# 07_USB.net
KiCad netlist of a schematic drawn in Altium Designer
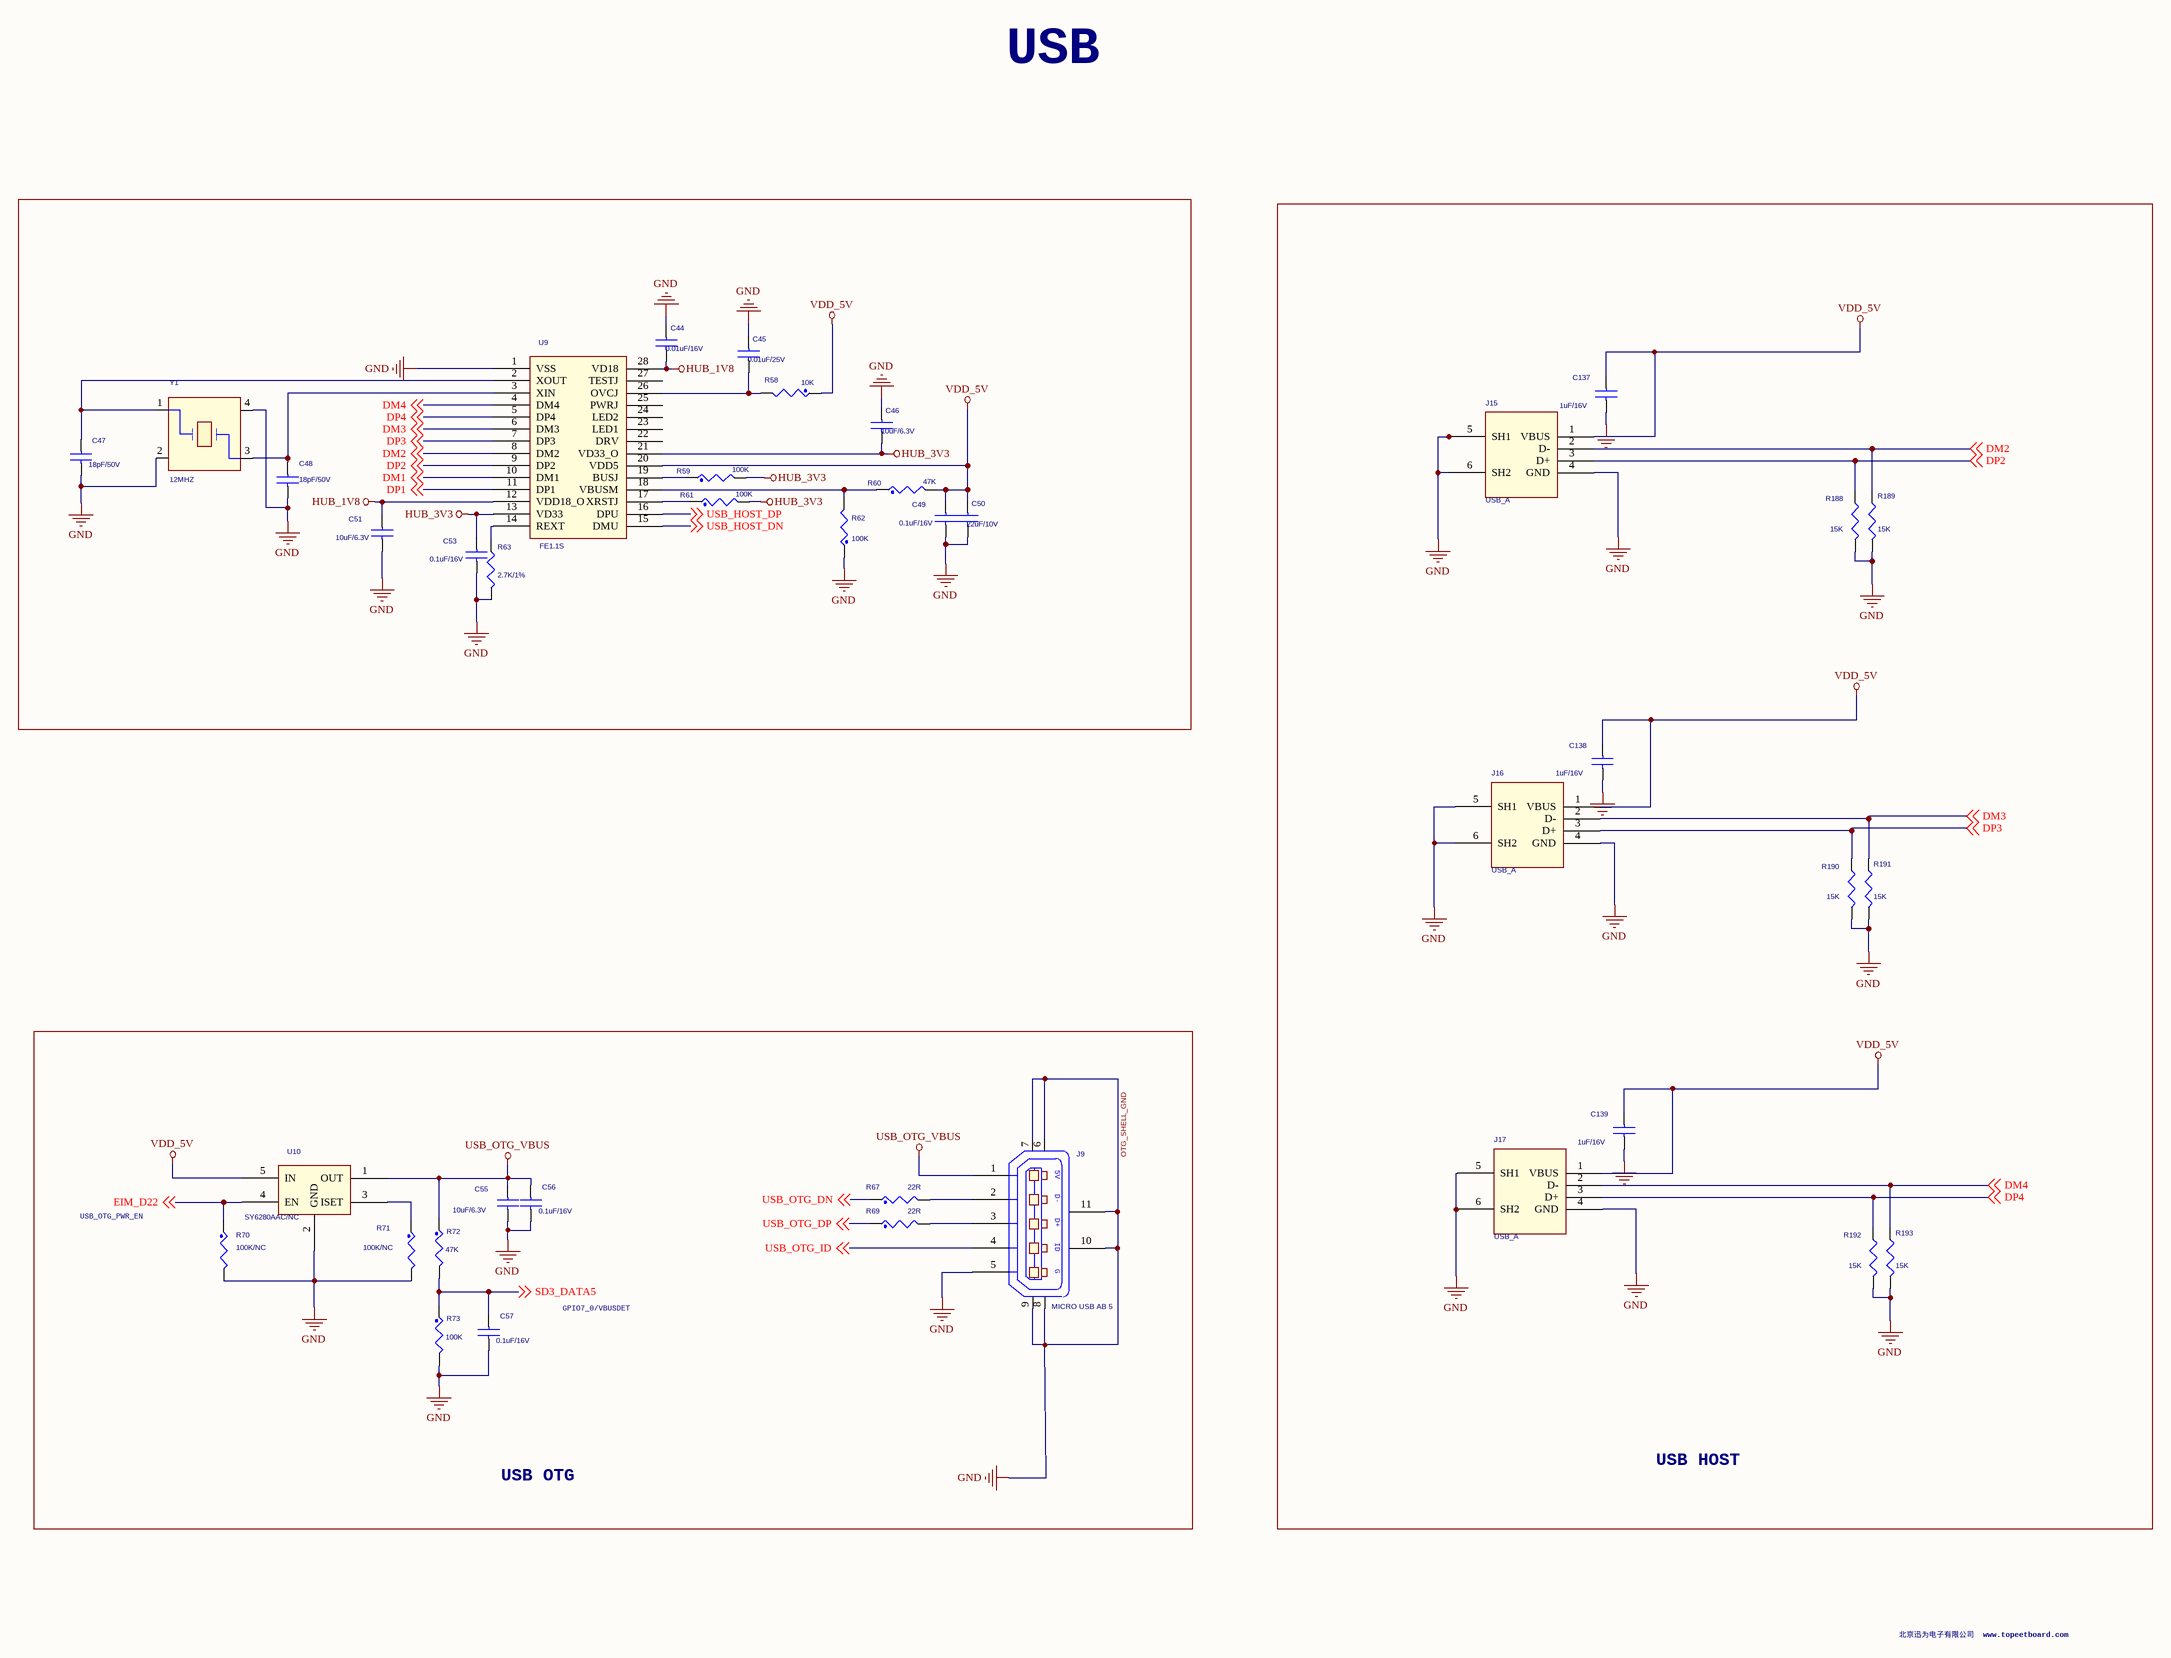
[diagram p0: 07 USB.SchDoc]

(export (version "E")
  (design (tool "Eeschema 10.0.6"))
  (components
    (comp (ref "C44") (value "0.01uF/16V") (footprint "C0603") (libsource (lib "*") (part "C0603_0_Dup1")))
    (comp (ref "C45") (value "0.01uF/25V") (footprint "C0603") (libsource (lib "*") (part "C0603_0_Dup1")))
    (comp (ref "C46") (value "10uF/6.3V") (footprint "C0603") (libsource (lib "*") (part "C0603_0_Dup1")))
    (comp (ref "C47") (value "18pF/50V") (footprint "C0603") (libsource (lib "*") (part "C0603_0_Dup1")))
    (comp (ref "C48") (value "18pF/50V") (footprint "C0603") (libsource (lib "*") (part "C0603_0_Dup1")))
    (comp (ref "C49") (value "0.1uF/16V") (footprint "C0603") (libsource (lib "*") (part "C0603_0_Dup1")))
    (comp (ref "C50") (value "22uF/10V") (footprint "C0603") (libsource (lib "*") (part "C0603_0_Dup1")))
    (comp (ref "C51") (value "10uF/6.3V") (footprint "C0603") (libsource (lib "*") (part "C0603_0_Dup1")))
    (comp (ref "C53") (value "0.1uF/16V") (footprint "C0603") (libsource (lib "*") (part "C0603_0_Dup1")))
    (comp (ref "C55") (value "10uF/6.3V") (footprint "C0603") (libsource (lib "*") (part "C0603_0_Dup1")))
    (comp (ref "C56") (value "0.1uF/16V") (footprint "C0603") (libsource (lib "*") (part "C0603_0_Dup1")))
    (comp (ref "C57") (value "0.1uF/16V") (footprint "C0603") (libsource (lib "*") (part "C0603_0_Dup1")))
    (comp (ref "C137") (value "1uF/16V") (footprint "C0603") (libsource (lib "*") (part "C0603_0_Dup1")))
    (comp (ref "C138") (value "1uF/16V") (footprint "C0603") (libsource (lib "*") (part "C0603_0_Dup1")))
    (comp (ref "C139") (value "1uF/16V") (footprint "C0603") (libsource (lib "*") (part "C0603_0_Dup1")))
    (comp (ref "J9")
      (value "MICRO USB AB 5")
      (description "CON 1X5 USB_MICRO_AB_RECEPTACLE RA SMT 0.65MM SP 105H AU")
      (libsource (lib "*") (part "USB_MINI_AB_RECEPTACLE_1"))
    )
    (comp (ref "J15") (value "USB_A") (libsource (lib "*") (part "USB")))
    (comp (ref "J16") (value "USB_A") (libsource (lib "*") (part "USB")))
    (comp (ref "J17") (value "USB_A") (libsource (lib "*") (part "USB")))
    (comp (ref "R58")
      (value "10K")
      (description "RES MF 10.0K 1/16W 1% AEC-Q200 0402")
      (fields (field (name "TOLERANCE") "1%"))
      (libsource (lib "*") (part "RES_Dup1"))
    )
    (comp (ref "R59")
      (value "100K")
      (description "RES MF 10.0K 1/16W 1% AEC-Q200 0402")
      (fields (field (name "TOLERANCE") "1%"))
      (libsource (lib "*") (part "RES_Dup1"))
    )
    (comp (ref "R60")
      (value "47K")
      (description "RES MF 10.0K 1/16W 1% AEC-Q200 0402")
      (fields (field (name "TOLERANCE") "1%"))
      (libsource (lib "*") (part "RES_Dup1"))
    )
    (comp (ref "R61")
      (value "100K")
      (description "RES MF 10.0K 1/16W 1% AEC-Q200 0402")
      (fields (field (name "TOLERANCE") "1%"))
      (libsource (lib "*") (part "RES_Dup1"))
    )
    (comp (ref "R62")
      (value "100K")
      (description "RES MF 10.0K 1/16W 1% AEC-Q200 0402")
      (fields (field (name "TOLERANCE") "1%"))
      (libsource (lib "*") (part "RES_Dup1"))
    )
    (comp (ref "R63") (value "2.7K/1%") (footprint "R1005") (libsource (lib "*") (part "R1005_0_Dup1")))
    (comp (ref "R67")
      (value "22R")
      (description "RES MF 10.0K 1/16W 1% AEC-Q200 0402")
      (fields (field (name "TOLERANCE") "1%"))
      (libsource (lib "*") (part "RES_Dup1"))
    )
    (comp (ref "R69")
      (value "22R")
      (description "RES MF 10.0K 1/16W 1% AEC-Q200 0402")
      (fields (field (name "TOLERANCE") "1%"))
      (libsource (lib "*") (part "RES_Dup1"))
    )
    (comp (ref "R70")
      (value "100K/NC")
      (description "RES MF 10.0K 1/16W 1% AEC-Q200 0402")
      (fields (field (name "TOLERANCE") "1%"))
      (libsource (lib "*") (part "RES_Dup1"))
    )
    (comp (ref "R71")
      (value "100K/NC")
      (description "RES MF 10.0K 1/16W 1% AEC-Q200 0402")
      (fields (field (name "TOLERANCE") "1%"))
      (libsource (lib "*") (part "RES_Dup1"))
    )
    (comp (ref "R72")
      (value "47K")
      (description "RES MF 10.0K 1/16W 1% AEC-Q200 0402")
      (fields (field (name "TOLERANCE") "1%"))
      (libsource (lib "*") (part "RES_Dup1"))
    )
    (comp (ref "R73")
      (value "100K")
      (description "RES MF 10.0K 1/16W 1% AEC-Q200 0402")
      (fields (field (name "TOLERANCE") "1%"))
      (libsource (lib "*") (part "RES_Dup1"))
    )
    (comp (ref "R188") (value "15K") (footprint "R1005") (libsource (lib "*") (part "R1005_0_Dup1")))
    (comp (ref "R189") (value "15K") (footprint "R1005") (libsource (lib "*") (part "R1005_0_Dup1")))
    (comp (ref "R190") (value "15K") (footprint "R1005") (libsource (lib "*") (part "R1005_0_Dup1")))
    (comp (ref "R191") (value "15K") (footprint "R1005") (libsource (lib "*") (part "R1005_0_Dup1")))
    (comp (ref "R192") (value "15K") (footprint "R1005") (libsource (lib "*") (part "R1005_0_Dup1")))
    (comp (ref "R193") (value "15K") (footprint "R1005") (libsource (lib "*") (part "R1005_0_Dup1")))
    (comp (ref "U9") (value "FE1.1S") (libsource (lib "*") (part "FE1.1S")))
    (comp (ref "U10") (value "SY6280AAC/NC") (libsource (lib "*") (part "SY6280AAC")))
    (comp (ref "Y1")
      (value "12MHZ")
      (description "XTAL 25MHZ -- -- SMT")
      (libsource (lib "*") (part "XTAL_13Y"))
    )
  )
  (nets
    (net (code "1") (name "DM1") (class "Default")
      (node (ref "U9") (pin "10") (pinfunction "DM1_10") (pintype "passive"))
    )
    (net (code "2") (name "DM2") (class "Default")
      (node (ref "J15") (pin "2") (pinfunction "D-_2") (pintype "passive"))
      (node (ref "R189") (pin "2") (pinfunction "2_2") (pintype "passive"))
      (node (ref "U9") (pin "8") (pinfunction "DM2_8") (pintype "passive"))
    )
    (net (code "3") (name "DM3") (class "Default")
      (node (ref "J16") (pin "2") (pinfunction "D-_2") (pintype "passive"))
      (node (ref "R191") (pin "2") (pinfunction "2_2") (pintype "passive"))
      (node (ref "U9") (pin "6") (pinfunction "DM3_6") (pintype "passive"))
    )
    (net (code "4") (name "DM4") (class "Default")
      (node (ref "J17") (pin "2") (pinfunction "D-_2") (pintype "passive"))
      (node (ref "R193") (pin "2") (pinfunction "2_2") (pintype "passive"))
      (node (ref "U9") (pin "4") (pinfunction "DM4_4") (pintype "passive"))
    )
    (net (code "5") (name "DP1") (class "Default")
      (node (ref "U9") (pin "11") (pinfunction "DP1_11") (pintype "passive"))
    )
    (net (code "6") (name "DP2") (class "Default")
      (node (ref "J15") (pin "3") (pinfunction "D+_3") (pintype "passive"))
      (node (ref "R188") (pin "2") (pinfunction "2_2") (pintype "passive"))
      (node (ref "U9") (pin "9") (pinfunction "DP2_9") (pintype "passive"))
    )
    (net (code "7") (name "DP3") (class "Default")
      (node (ref "J16") (pin "3") (pinfunction "D+_3") (pintype "passive"))
      (node (ref "R190") (pin "2") (pinfunction "2_2") (pintype "passive"))
      (node (ref "U9") (pin "7") (pinfunction "DP3_7") (pintype "passive"))
    )
    (net (code "8") (name "DP4") (class "Default")
      (node (ref "J17") (pin "3") (pinfunction "D+_3") (pintype "passive"))
      (node (ref "R192") (pin "2") (pinfunction "2_2") (pintype "passive"))
      (node (ref "U9") (pin "5") (pinfunction "DP4_5") (pintype "passive"))
    )
    (net (code "9") (name "EIM_D22") (class "Default")
      (node (ref "R70") (pin "1") (pinfunction "1_1") (pintype "passive"))
      (node (ref "U10") (pin "4") (pinfunction "EN_4") (pintype "passive"))
    )
    (net (code "10") (name "GND") (class "Default")
      (node (ref "C137") (pin "2") (pinfunction "2_2") (pintype "passive"))
      (node (ref "C138") (pin "2") (pinfunction "2_2") (pintype "passive"))
      (node (ref "C139") (pin "2") (pinfunction "2_2") (pintype "passive"))
      (node (ref "C44") (pin "1") (pinfunction "1_1") (pintype "passive"))
      (node (ref "C45") (pin "1") (pinfunction "1_1") (pintype "passive"))
      (node (ref "C46") (pin "1") (pinfunction "1_1") (pintype "passive"))
      (node (ref "C47") (pin "2") (pinfunction "2_2") (pintype "passive"))
      (node (ref "C48") (pin "2") (pinfunction "2_2") (pintype "passive"))
      (node (ref "C49") (pin "2") (pinfunction "2_2") (pintype "passive"))
      (node (ref "C50") (pin "2") (pinfunction "2_2") (pintype "passive"))
      (node (ref "C51") (pin "2") (pinfunction "2_2") (pintype "passive"))
      (node (ref "C53") (pin "2") (pinfunction "2_2") (pintype "passive"))
      (node (ref "C55") (pin "2") (pinfunction "2_2") (pintype "passive"))
      (node (ref "C56") (pin "2") (pinfunction "2_2") (pintype "passive"))
      (node (ref "C57") (pin "2") (pinfunction "2_2") (pintype "passive"))
      (node (ref "J15") (pin "4") (pinfunction "GND_4") (pintype "passive"))
      (node (ref "J15") (pin "5") (pinfunction "SH1_5") (pintype "passive"))
      (node (ref "J15") (pin "6") (pinfunction "SH2_6") (pintype "passive"))
      (node (ref "J16") (pin "4") (pinfunction "GND_4") (pintype "passive"))
      (node (ref "J16") (pin "5") (pinfunction "SH1_5") (pintype "passive"))
      (node (ref "J16") (pin "6") (pinfunction "SH2_6") (pintype "passive"))
      (node (ref "J17") (pin "4") (pinfunction "GND_4") (pintype "passive"))
      (node (ref "J17") (pin "5") (pinfunction "SH1_5") (pintype "passive"))
      (node (ref "J17") (pin "6") (pinfunction "SH2_6") (pintype "passive"))
      (node (ref "J9") (pin "10") (pinfunction "SHLD5_10") (pintype "passive"))
      (node (ref "J9") (pin "11") (pinfunction "SHLD6_11") (pintype "passive"))
      (node (ref "J9") (pin "5") (pinfunction "P5_5") (pintype "passive"))
      (node (ref "J9") (pin "6") (pinfunction "SHLD1_6") (pintype "passive"))
      (node (ref "J9") (pin "7") (pinfunction "SHLD3_7") (pintype "passive"))
      (node (ref "J9") (pin "8") (pinfunction "SHLD2_8") (pintype "passive"))
      (node (ref "J9") (pin "9") (pinfunction "SHLD4_9") (pintype "passive"))
      (node (ref "R188") (pin "1") (pinfunction "1_1") (pintype "passive"))
      (node (ref "R189") (pin "1") (pinfunction "1_1") (pintype "passive"))
      (node (ref "R190") (pin "1") (pinfunction "1_1") (pintype "passive"))
      (node (ref "R191") (pin "1") (pinfunction "1_1") (pintype "passive"))
      (node (ref "R192") (pin "1") (pinfunction "1_1") (pintype "passive"))
      (node (ref "R193") (pin "1") (pinfunction "1_1") (pintype "passive"))
      (node (ref "R62") (pin "1") (pinfunction "1_1") (pintype "passive"))
      (node (ref "R63") (pin "1") (pinfunction "1_1") (pintype "passive"))
      (node (ref "R70") (pin "2") (pinfunction "2_2") (pintype "passive"))
      (node (ref "R71") (pin "2") (pinfunction "2_2") (pintype "passive"))
      (node (ref "R73") (pin "2") (pinfunction "2_2") (pintype "passive"))
      (node (ref "U10") (pin "2") (pinfunction "GND_2") (pintype "passive"))
      (node (ref "U9") (pin "1") (pinfunction "VSS_1") (pintype "passive"))
      (node (ref "Y1") (pin "2") (pinfunction "2_2") (pintype "passive"))
      (node (ref "Y1") (pin "4") (pinfunction "4_4") (pintype "passive"))
    )
    (net (code "11") (name "HUB_1V8") (class "Default")
      (node (ref "C44") (pin "2") (pinfunction "2_2") (pintype "passive"))
      (node (ref "C51") (pin "1") (pinfunction "1_1") (pintype "passive"))
      (node (ref "U9") (pin "12") (pinfunction "VDD18_O_12") (pintype "passive"))
      (node (ref "U9") (pin "28") (pinfunction "VD18_28") (pintype "passive"))
    )
    (net (code "12") (name "HUB_3V3") (class "Default")
      (node (ref "C46") (pin "2") (pinfunction "2_2") (pintype "passive"))
      (node (ref "C53") (pin "1") (pinfunction "1_1") (pintype "passive"))
      (node (ref "R59") (pin "2") (pinfunction "2_2") (pintype "passive"))
      (node (ref "R61") (pin "2") (pinfunction "2_2") (pintype "passive"))
      (node (ref "U9") (pin "13") (pinfunction "VD33_13") (pintype "passive"))
      (node (ref "U9") (pin "21") (pinfunction "VD33_O_21") (pintype "passive"))
    )
    (net (code "13") (name "Net-(J9-P2)") (class "Default")
      (node (ref "J9") (pin "2") (pinfunction "P2_2") (pintype "passive"))
      (node (ref "R67") (pin "2") (pinfunction "2_2") (pintype "passive"))
    )
    (net (code "14") (name "Net-(J9-P3)") (class "Default")
      (node (ref "J9") (pin "3") (pinfunction "P3_3") (pintype "passive"))
      (node (ref "R69") (pin "2") (pinfunction "2_2") (pintype "passive"))
    )
    (net (code "15") (name "Net-(U9-BUSJ)") (class "Default")
      (node (ref "R59") (pin "1") (pinfunction "1_1") (pintype "passive"))
      (node (ref "U9") (pin "19") (pinfunction "BUSJ_19") (pintype "passive"))
    )
    (net (code "16") (name "Net-(U9-OVCJ)") (class "Default")
      (node (ref "C45") (pin "2") (pinfunction "2_2") (pintype "passive"))
      (node (ref "R58") (pin "2") (pinfunction "2_2") (pintype "passive"))
      (node (ref "U9") (pin "26") (pinfunction "OVCJ_26") (pintype "passive"))
    )
    (net (code "17") (name "Net-(U9-REXT)") (class "Default")
      (node (ref "R63") (pin "2") (pinfunction "2_2") (pintype "passive"))
      (node (ref "U9") (pin "14") (pinfunction "REXT_14") (pintype "passive"))
    )
    (net (code "18") (name "Net-(U9-VBUSM)") (class "Default")
      (node (ref "R60") (pin "1") (pinfunction "1_1") (pintype "passive"))
      (node (ref "R62") (pin "2") (pinfunction "2_2") (pintype "passive"))
      (node (ref "U9") (pin "18") (pinfunction "VBUSM_18") (pintype "passive"))
    )
    (net (code "19") (name "Net-(U9-XIN)") (class "Default")
      (node (ref "C48") (pin "1") (pinfunction "1_1") (pintype "passive"))
      (node (ref "U9") (pin "3") (pinfunction "XIN_3") (pintype "passive"))
      (node (ref "Y1") (pin "3") (pinfunction "3_3") (pintype "passive"))
    )
    (net (code "20") (name "Net-(U9-XOUT)") (class "Default")
      (node (ref "C47") (pin "1") (pinfunction "1_1") (pintype "passive"))
      (node (ref "U9") (pin "2") (pinfunction "XOUT_2") (pintype "passive"))
      (node (ref "Y1") (pin "1") (pinfunction "1_1") (pintype "passive"))
    )
    (net (code "21") (name "Net-(U9-XRSTJ)") (class "Default")
      (node (ref "R61") (pin "1") (pinfunction "1_1") (pintype "passive"))
      (node (ref "U9") (pin "17") (pinfunction "XRSTJ_17") (pintype "passive"))
    )
    (net (code "22") (name "Net-(U10-ISET)") (class "Default")
      (node (ref "R71") (pin "1") (pinfunction "1_1") (pintype "passive"))
      (node (ref "U10") (pin "3") (pinfunction "ISET_3") (pintype "passive"))
    )
    (net (code "23") (name "SD3_DATA5") (class "Default")
      (node (ref "C57") (pin "1") (pinfunction "1_1") (pintype "passive"))
      (node (ref "R72") (pin "2") (pinfunction "2_2") (pintype "passive"))
      (node (ref "R73") (pin "1") (pinfunction "1_1") (pintype "passive"))
    )
    (net (code "24") (name "USB_HOST_DN") (class "Default")
      (node (ref "U9") (pin "15") (pinfunction "DMU_15") (pintype "passive"))
    )
    (net (code "25") (name "USB_HOST_DP") (class "Default")
      (node (ref "U9") (pin "16") (pinfunction "DPU_16") (pintype "passive"))
    )
    (net (code "26") (name "USB_OTG_DN") (class "Default")
      (node (ref "R67") (pin "1") (pinfunction "1_1") (pintype "passive"))
    )
    (net (code "27") (name "USB_OTG_DP") (class "Default")
      (node (ref "R69") (pin "1") (pinfunction "1_1") (pintype "passive"))
    )
    (net (code "28") (name "USB_OTG_ID") (class "Default")
      (node (ref "J9") (pin "4") (pinfunction "P4_4") (pintype "passive"))
    )
    (net (code "29") (name "USB_OTG_VBUS") (class "Default")
      (node (ref "C55") (pin "1") (pinfunction "1_1") (pintype "passive"))
      (node (ref "C56") (pin "1") (pinfunction "1_1") (pintype "passive"))
      (node (ref "J9") (pin "1") (pinfunction "P1_1") (pintype "passive"))
      (node (ref "R72") (pin "1") (pinfunction "1_1") (pintype "passive"))
      (node (ref "U10") (pin "1") (pinfunction "OUT_1") (pintype "passive"))
    )
    (net (code "30") (name "VDD_5V") (class "Default")
      (node (ref "C137") (pin "1") (pinfunction "1_1") (pintype "passive"))
      (node (ref "C138") (pin "1") (pinfunction "1_1") (pintype "passive"))
      (node (ref "C139") (pin "1") (pinfunction "1_1") (pintype "passive"))
      (node (ref "C49") (pin "1") (pinfunction "1_1") (pintype "passive"))
      (node (ref "C50") (pin "1") (pinfunction "1_1") (pintype "passive"))
      (node (ref "J15") (pin "1") (pinfunction "VBUS_1") (pintype "passive"))
      (node (ref "J16") (pin "1") (pinfunction "VBUS_1") (pintype "passive"))
      (node (ref "J17") (pin "1") (pinfunction "VBUS_1") (pintype "passive"))
      (node (ref "R58") (pin "1") (pinfunction "1_1") (pintype "passive"))
      (node (ref "R60") (pin "2") (pinfunction "2_2") (pintype "passive"))
      (node (ref "U10") (pin "5") (pinfunction "IN_5") (pintype "passive"))
      (node (ref "U9") (pin "20") (pinfunction "VDD5_20") (pintype "passive"))
    )
    (net (code "31") (name "unconnected-(U9-DRV-Pad22)") (class "Default")
      (node (ref "U9") (pin "22") (pinfunction "DRV_22") (pintype "passive"))
    )
    (net (code "32") (name "unconnected-(U9-LED1-Pad23)") (class "Default")
      (node (ref "U9") (pin "23") (pinfunction "LED1_23") (pintype "passive"))
    )
    (net (code "33") (name "unconnected-(U9-LED2-Pad24)") (class "Default")
      (node (ref "U9") (pin "24") (pinfunction "LED2_24") (pintype "passive"))
    )
    (net (code "34") (name "unconnected-(U9-PWRJ-Pad25)") (class "Default")
      (node (ref "U9") (pin "25") (pinfunction "PWRJ_25") (pintype "passive"))
    )
    (net (code "35") (name "unconnected-(U9-TESTJ-Pad27)") (class "Default")
      (node (ref "U9") (pin "27") (pinfunction "TESTJ_27") (pintype "passive"))
    )
  )
)
